# single.net
KiCad netlist of a schematic drawn in EAGLE
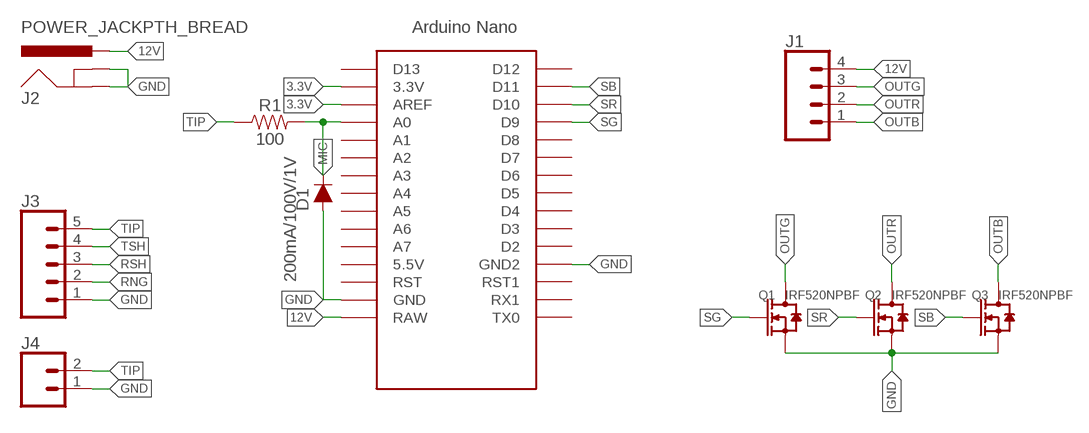
[diagram p0: schematic, sheet 1]

(export (version "E")
  (design (tool "Eeschema 10.0.6"))
  (components
    (comp (ref "D1")
      (value "200mA/100V/1V")
      (footprint "eagle-import:DIODE-1N4148")
      (libsource (lib "eagle-import") (part "DIODE-1N4148"))
    )
    (comp (ref "J1")
      (value "CONN_04LOCK_LONGPADS")
      (footprint "eagle-import:1X04_LOCK_LONGPADS")
      (libsource (lib "eagle-import") (part "CONN_04LOCK_LONGPADS"))
    )
    (comp (ref "J2")
      (value "POWER_JACKPTH_BREAD")
      (footprint "eagle-import:POWER_JACK_PTH_BREAD")
      (libsource (lib "eagle-import") (part "POWER_JACKPTH_BREAD"))
    )
    (comp (ref "J3")
      (value "CONN_05LOCK_LONGPADS")
      (footprint "eagle-import:1X05_LOCK_LONGPADS")
      (libsource (lib "eagle-import") (part "CONN_05LOCK_LONGPADS"))
    )
    (comp (ref "J4")
      (value "CONN_02LOCK_LONGPADS")
      (footprint "eagle-import:1X02_LOCK_LONGPADS")
      (libsource (lib "eagle-import") (part "CONN_02LOCK_LONGPADS"))
    )
    (comp (ref "Q1")
      (value "IRF520NPBF")
      (footprint "eagle-import:TO-220")
      (libsource (lib "eagle-import") (part "DIP-MOSFET-N-CH-100V-9.7A-IRF520NPBF(TO-220AB)"))
    )
    (comp (ref "Q2")
      (value "IRF520NPBF")
      (footprint "eagle-import:TO-220")
      (libsource (lib "eagle-import") (part "DIP-MOSFET-N-CH-100V-9.7A-IRF520NPBF(TO-220AB)"))
    )
    (comp (ref "Q3")
      (value "IRF520NPBF")
      (footprint "eagle-import:TO-220")
      (libsource (lib "eagle-import") (part "DIP-MOSFET-N-CH-100V-9.7A-IRF520NPBF(TO-220AB)"))
    )
    (comp (ref "R1")
      (value "100")
      (footprint "eagle-import:AXIAL-0.3")
      (libsource (lib "eagle-import") (part "100OHM-HORIZ-1/4W-1%"))
    )
    (comp (ref "U$1")
      (value "NANONOICSP")
      (footprint "eagle-import:NANO_2")
      (libsource (lib "eagle-import") (part "NANONOICSP"))
    )
  )
  (nets
    (net (code "1") (name "3.3V") (class "Default")
      (node (ref "U$1") (pin "3.3V") (pinfunction "3.3V_3.3V") (pintype "bidirectional"))
      (node (ref "U$1") (pin "AREF") (pinfunction "AREF_AREF") (pintype "bidirectional"))
    )
    (net (code "2") (name "12V") (class "Default")
      (node (ref "J1") (pin "4") (pinfunction "4_4") (pintype "passive"))
      (node (ref "J2") (pin "PWR") (pinfunction "PWR_PWR") (pintype "bidirectional"))
      (node (ref "U$1") (pin "RAW") (pinfunction "RAW_RAW") (pintype "bidirectional"))
    )
    (net (code "3") (name "GND") (class "Default")
      (node (ref "D1") (pin "A") (pinfunction "A_A") (pintype "passive"))
      (node (ref "J2") (pin "GND") (pinfunction "GND_GND") (pintype "bidirectional"))
      (node (ref "J2") (pin "GNDBREAK") (pinfunction "GNDBREAK_GNDBREAK") (pintype "bidirectional"))
      (node (ref "J3") (pin "1") (pinfunction "1_1") (pintype "passive"))
      (node (ref "J4") (pin "1") (pinfunction "1_1") (pintype "passive"))
      (node (ref "Q1") (pin "2") (pinfunction "S_2") (pintype "passive"))
      (node (ref "Q1") (pin "HEAT") (pinfunction "S_HEAT") (pintype "passive"))
      (node (ref "Q2") (pin "2") (pinfunction "S_2") (pintype "passive"))
      (node (ref "Q2") (pin "HEAT") (pinfunction "S_HEAT") (pintype "passive"))
      (node (ref "Q3") (pin "2") (pinfunction "S_2") (pintype "passive"))
      (node (ref "Q3") (pin "HEAT") (pinfunction "S_HEAT") (pintype "passive"))
      (node (ref "U$1") (pin "GND") (pinfunction "GND_GND") (pintype "bidirectional"))
      (node (ref "U$1") (pin "GND1") (pinfunction "GND2_GND1") (pintype "bidirectional"))
    )
    (net (code "4") (name "MIC") (class "Default")
      (node (ref "D1") (pin "C") (pinfunction "C_C") (pintype "passive"))
      (node (ref "R1") (pin "P$2") (pinfunction "2_P$2") (pintype "passive"))
      (node (ref "U$1") (pin "A0") (pinfunction "A0_A0") (pintype "bidirectional"))
    )
    (net (code "5") (name "OUTB") (class "Default")
      (node (ref "J1") (pin "1") (pinfunction "1_1") (pintype "passive"))
      (node (ref "Q3") (pin "3") (pinfunction "D_3") (pintype "passive"))
    )
    (net (code "6") (name "OUTG") (class "Default")
      (node (ref "J1") (pin "3") (pinfunction "3_3") (pintype "passive"))
      (node (ref "Q1") (pin "3") (pinfunction "D_3") (pintype "passive"))
    )
    (net (code "7") (name "OUTR") (class "Default")
      (node (ref "J1") (pin "2") (pinfunction "2_2") (pintype "passive"))
      (node (ref "Q2") (pin "3") (pinfunction "D_3") (pintype "passive"))
    )
    (net (code "8") (name "RNG") (class "Default")
      (node (ref "J3") (pin "2") (pinfunction "2_2") (pintype "passive"))
    )
    (net (code "9") (name "RSH") (class "Default")
      (node (ref "J3") (pin "3") (pinfunction "3_3") (pintype "passive"))
    )
    (net (code "10") (name "SB") (class "Default")
      (node (ref "Q3") (pin "1") (pinfunction "G_1") (pintype "passive"))
      (node (ref "U$1") (pin "D11") (pinfunction "D11_D11") (pintype "bidirectional"))
    )
    (net (code "11") (name "SG") (class "Default")
      (node (ref "Q1") (pin "1") (pinfunction "G_1") (pintype "passive"))
      (node (ref "U$1") (pin "D9") (pinfunction "D9_D9") (pintype "bidirectional"))
    )
    (net (code "12") (name "SR") (class "Default")
      (node (ref "Q2") (pin "1") (pinfunction "G_1") (pintype "passive"))
      (node (ref "U$1") (pin "D10") (pinfunction "D10_D10") (pintype "bidirectional"))
    )
    (net (code "13") (name "TIP") (class "Default")
      (node (ref "J3") (pin "5") (pinfunction "5_5") (pintype "passive"))
      (node (ref "J4") (pin "2") (pinfunction "2_2") (pintype "passive"))
      (node (ref "R1") (pin "P$1") (pinfunction "1_P$1") (pintype "passive"))
    )
    (net (code "14") (name "TSH") (class "Default")
      (node (ref "J3") (pin "4") (pinfunction "4_4") (pintype "passive"))
    )
    (net (code "15") (name "unconnected-(U$1-5.5V-Pad5V)") (class "Default")
      (node (ref "U$1") (pin "5V") (pinfunction "5.5V_5V") (pintype "bidirectional"))
    )
    (net (code "16") (name "unconnected-(U$1-PadA1)") (class "Default")
      (node (ref "U$1") (pin "A1") (pinfunction "A1_A1") (pintype "bidirectional"))
    )
    (net (code "17") (name "unconnected-(U$1-PadA2)") (class "Default")
      (node (ref "U$1") (pin "A2") (pinfunction "A2_A2") (pintype "bidirectional"))
    )
    (net (code "18") (name "unconnected-(U$1-PadA3)") (class "Default")
      (node (ref "U$1") (pin "A3") (pinfunction "A3_A3") (pintype "bidirectional"))
    )
    (net (code "19") (name "unconnected-(U$1-PadA4)") (class "Default")
      (node (ref "U$1") (pin "A4") (pinfunction "A4_A4") (pintype "bidirectional"))
    )
    (net (code "20") (name "unconnected-(U$1-PadA5)") (class "Default")
      (node (ref "U$1") (pin "A5") (pinfunction "A5_A5") (pintype "bidirectional"))
    )
    (net (code "21") (name "unconnected-(U$1-PadA6)") (class "Default")
      (node (ref "U$1") (pin "A6") (pinfunction "A6_A6") (pintype "bidirectional"))
    )
    (net (code "22") (name "unconnected-(U$1-PadA7)") (class "Default")
      (node (ref "U$1") (pin "A7") (pinfunction "A7_A7") (pintype "bidirectional"))
    )
    (net (code "23") (name "unconnected-(U$1-PadD2)") (class "Default")
      (node (ref "U$1") (pin "D2") (pinfunction "D2_D2") (pintype "bidirectional"))
    )
    (net (code "24") (name "unconnected-(U$1-PadD3)") (class "Default")
      (node (ref "U$1") (pin "D3") (pinfunction "D3_D3") (pintype "bidirectional"))
    )
    (net (code "25") (name "unconnected-(U$1-PadD4)") (class "Default")
      (node (ref "U$1") (pin "D4") (pinfunction "D4_D4") (pintype "bidirectional"))
    )
    (net (code "26") (name "unconnected-(U$1-PadD5)") (class "Default")
      (node (ref "U$1") (pin "D5") (pinfunction "D5_D5") (pintype "bidirectional"))
    )
    (net (code "27") (name "unconnected-(U$1-PadD6)") (class "Default")
      (node (ref "U$1") (pin "D6") (pinfunction "D6_D6") (pintype "bidirectional"))
    )
    (net (code "28") (name "unconnected-(U$1-PadD7)") (class "Default")
      (node (ref "U$1") (pin "D7") (pinfunction "D7_D7") (pintype "bidirectional"))
    )
    (net (code "29") (name "unconnected-(U$1-PadD8)") (class "Default")
      (node (ref "U$1") (pin "D8") (pinfunction "D8_D8") (pintype "bidirectional"))
    )
    (net (code "30") (name "unconnected-(U$1-PadD12)") (class "Default")
      (node (ref "U$1") (pin "D12") (pinfunction "D12_D12") (pintype "bidirectional"))
    )
    (net (code "31") (name "unconnected-(U$1-PadD13)") (class "Default")
      (node (ref "U$1") (pin "D13") (pinfunction "D13_D13") (pintype "bidirectional"))
    )
    (net (code "32") (name "unconnected-(U$1-PadRST)") (class "Default")
      (node (ref "U$1") (pin "RST") (pinfunction "RST_RST") (pintype "bidirectional"))
    )
    (net (code "33") (name "unconnected-(U$1-PadRST1)") (class "Default")
      (node (ref "U$1") (pin "RST1") (pinfunction "RST1_RST1") (pintype "bidirectional"))
    )
    (net (code "34") (name "unconnected-(U$1-PadRX1)") (class "Default")
      (node (ref "U$1") (pin "RX1") (pinfunction "RX1_RX1") (pintype "bidirectional"))
    )
    (net (code "35") (name "unconnected-(U$1-PadTX0)") (class "Default")
      (node (ref "U$1") (pin "TX0") (pinfunction "TX0_TX0") (pintype "bidirectional"))
    )
  )
)
